# Current_DAC.net
KiCad netlist of a schematic drawn in Altium Designer
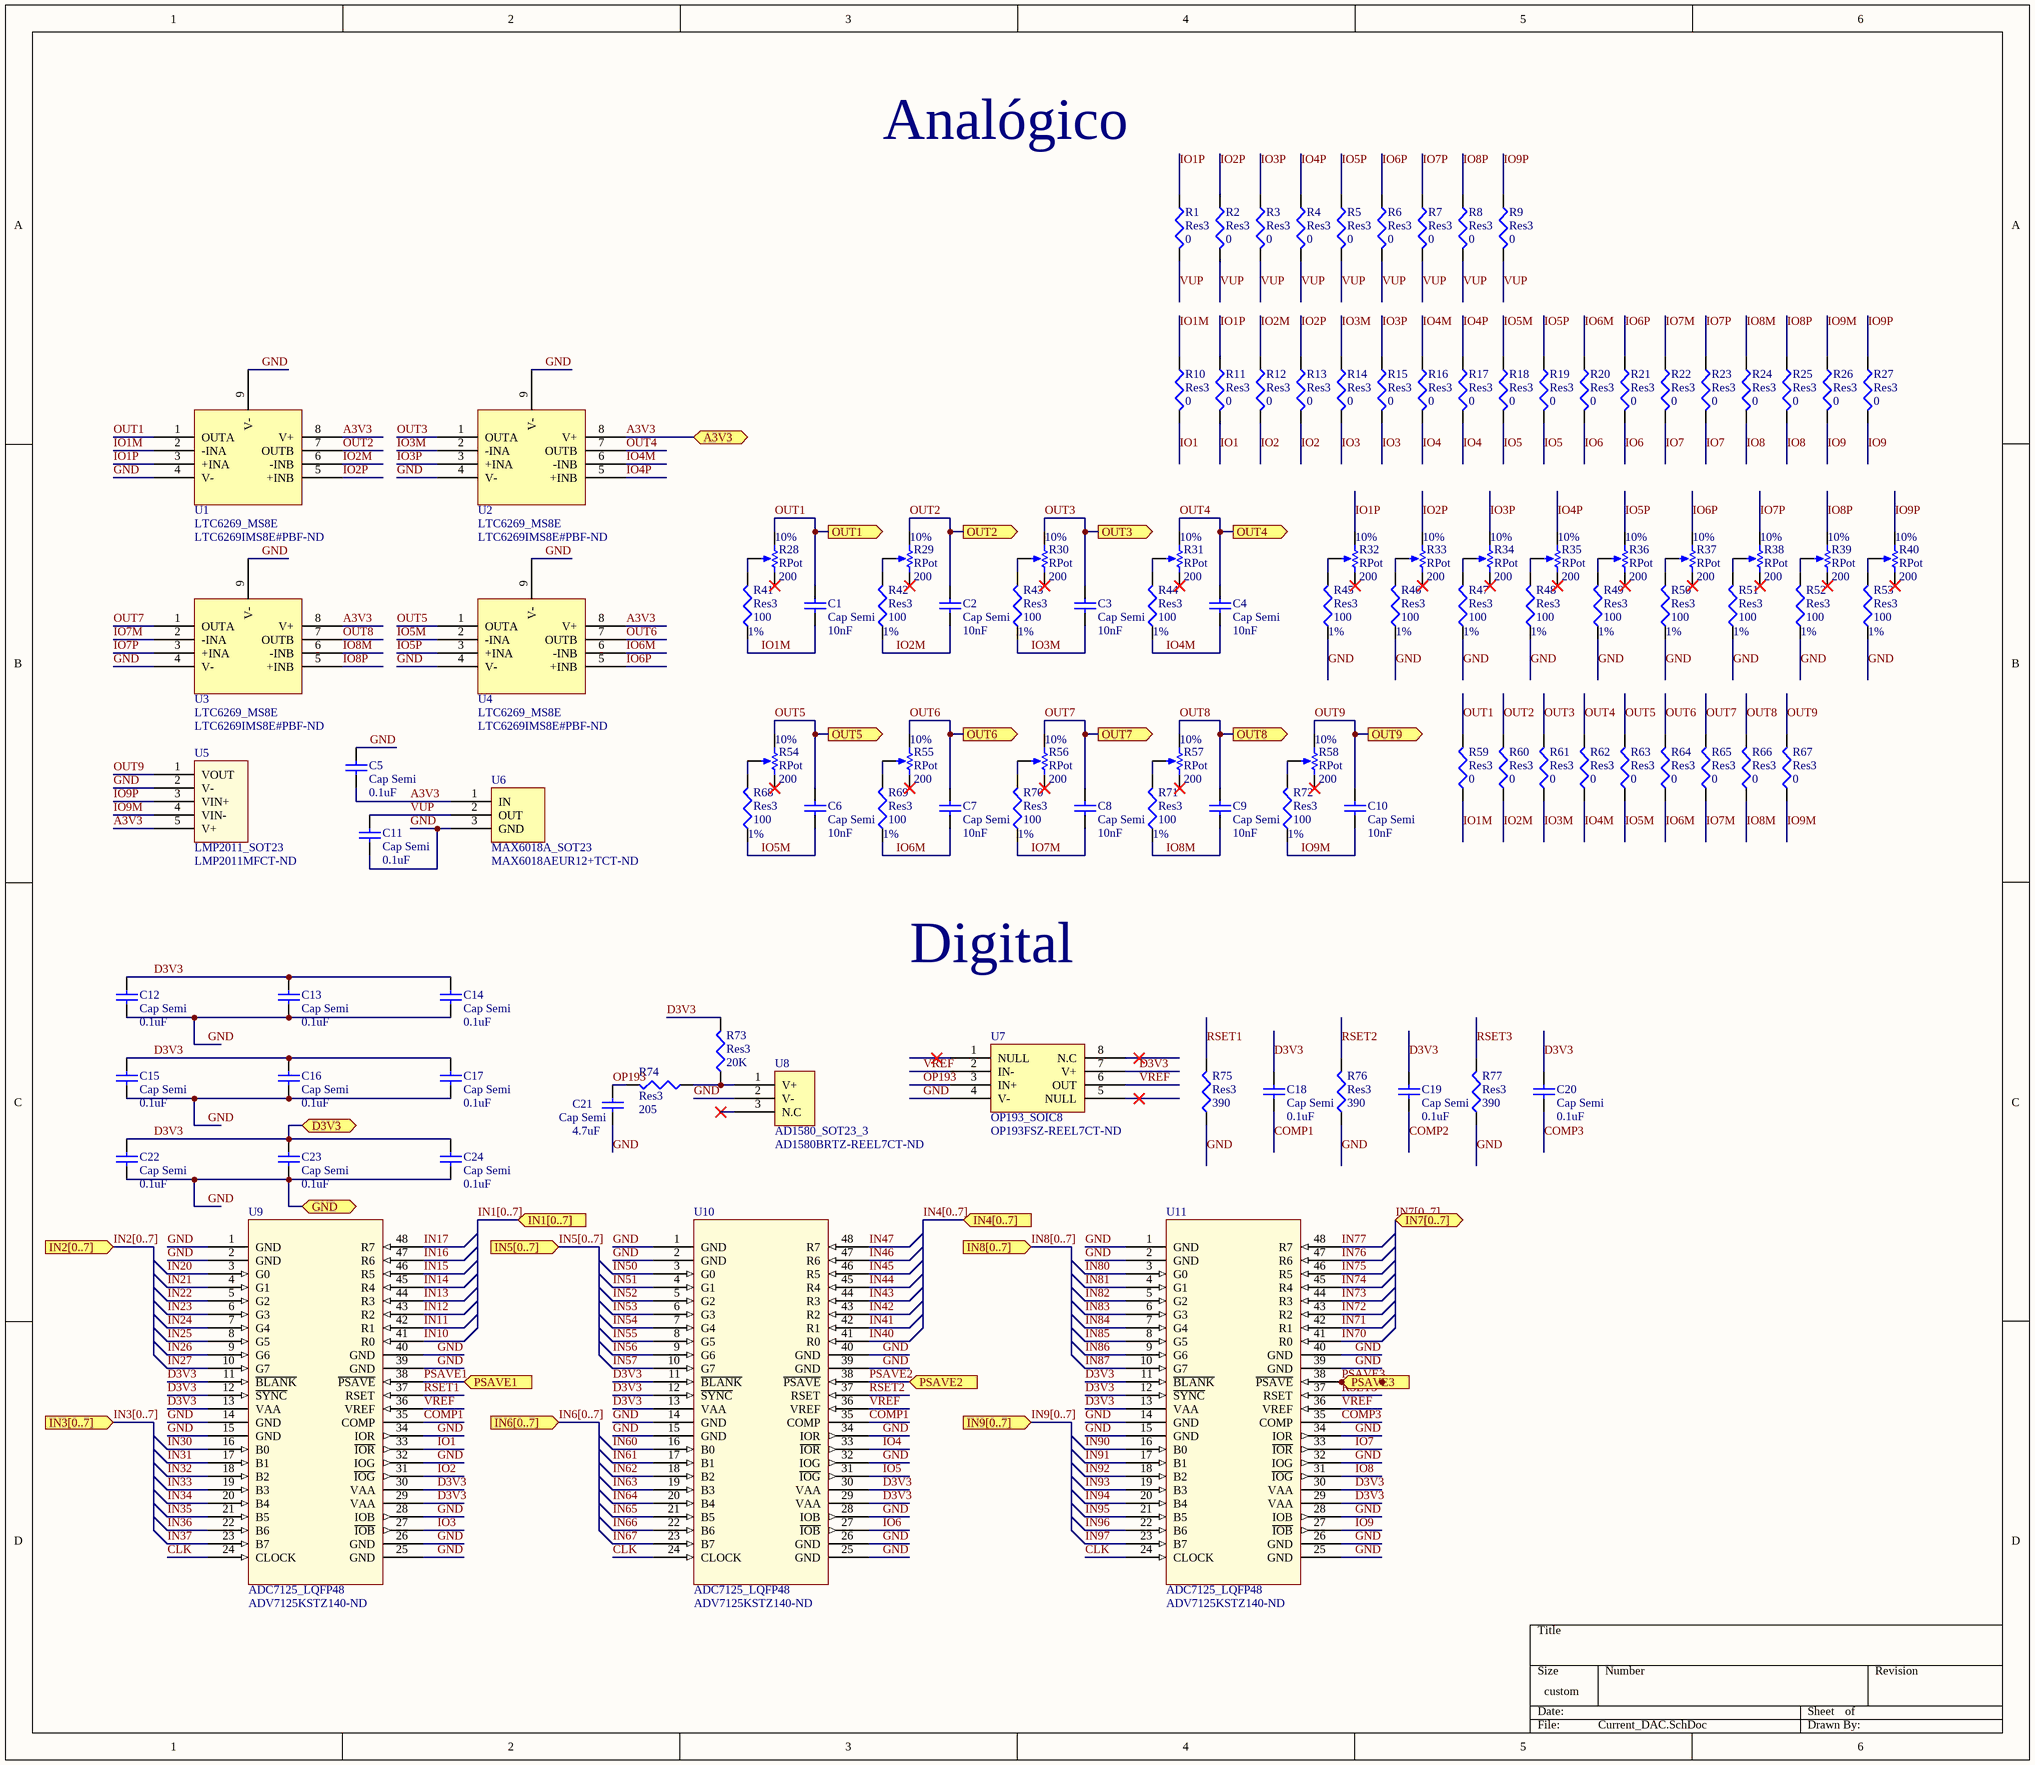
[diagram p0: Current_DAC.SchDoc]

(export (version "E")
  (design (tool "Eeschema 10.0.6"))
  (components
    (comp (ref "C1")
      (value "Cap Semi")
      (footprint "J1-0603")
      (description "Capacitor (Semiconductor SIM Model)")
      (fields (field (name "ALTIUM_VALUE") "10nF") (field (name "PUBLISHER") "Altium Limited"))
      (libsource (lib "Miscellaneous Devices") (part "Cap Semi"))
    )
    (comp (ref "C2")
      (value "Cap Semi")
      (footprint "J1-0603")
      (description "Capacitor (Semiconductor SIM Model)")
      (fields (field (name "ALTIUM_VALUE") "10nF") (field (name "PUBLISHER") "Altium Limited"))
      (libsource (lib "Miscellaneous Devices") (part "Cap Semi"))
    )
    (comp (ref "C3")
      (value "Cap Semi")
      (footprint "J1-0603")
      (description "Capacitor (Semiconductor SIM Model)")
      (fields (field (name "ALTIUM_VALUE") "10nF") (field (name "PUBLISHER") "Altium Limited"))
      (libsource (lib "Miscellaneous Devices") (part "Cap Semi"))
    )
    (comp (ref "C4")
      (value "Cap Semi")
      (footprint "J1-0603")
      (description "Capacitor (Semiconductor SIM Model)")
      (fields (field (name "ALTIUM_VALUE") "10nF") (field (name "PUBLISHER") "Altium Limited"))
      (libsource (lib "Miscellaneous Devices") (part "Cap Semi"))
    )
    (comp (ref "C5")
      (value "Cap Semi")
      (footprint "J1-0603")
      (description "Capacitor (Semiconductor SIM Model)")
      (fields (field (name "ALTIUM_VALUE") "0.1uF") (field (name "PUBLISHER") "Altium Limited"))
      (libsource (lib "Miscellaneous Devices") (part "Cap Semi"))
    )
    (comp (ref "C6")
      (value "Cap Semi")
      (footprint "J1-0603")
      (description "Capacitor (Semiconductor SIM Model)")
      (fields (field (name "ALTIUM_VALUE") "10nF") (field (name "PUBLISHER") "Altium Limited"))
      (libsource (lib "Miscellaneous Devices") (part "Cap Semi"))
    )
    (comp (ref "C7")
      (value "Cap Semi")
      (footprint "J1-0603")
      (description "Capacitor (Semiconductor SIM Model)")
      (fields (field (name "ALTIUM_VALUE") "10nF") (field (name "PUBLISHER") "Altium Limited"))
      (libsource (lib "Miscellaneous Devices") (part "Cap Semi"))
    )
    (comp (ref "C8")
      (value "Cap Semi")
      (footprint "J1-0603")
      (description "Capacitor (Semiconductor SIM Model)")
      (fields (field (name "ALTIUM_VALUE") "10nF") (field (name "PUBLISHER") "Altium Limited"))
      (libsource (lib "Miscellaneous Devices") (part "Cap Semi"))
    )
    (comp (ref "C9")
      (value "Cap Semi")
      (footprint "J1-0603")
      (description "Capacitor (Semiconductor SIM Model)")
      (fields (field (name "ALTIUM_VALUE") "10nF") (field (name "PUBLISHER") "Altium Limited"))
      (libsource (lib "Miscellaneous Devices") (part "Cap Semi"))
    )
    (comp (ref "C10")
      (value "Cap Semi")
      (footprint "J1-0603")
      (description "Capacitor (Semiconductor SIM Model)")
      (fields (field (name "ALTIUM_VALUE") "10nF") (field (name "PUBLISHER") "Altium Limited"))
      (libsource (lib "Miscellaneous Devices") (part "Cap Semi"))
    )
    (comp (ref "C11")
      (value "Cap Semi")
      (footprint "J1-0603")
      (description "Capacitor (Semiconductor SIM Model)")
      (fields (field (name "ALTIUM_VALUE") "0.1uF") (field (name "PUBLISHER") "Altium Limited"))
      (libsource (lib "Miscellaneous Devices") (part "Cap Semi"))
    )
    (comp (ref "C12")
      (value "Cap Semi")
      (footprint "J1-0603")
      (description "Capacitor (Semiconductor SIM Model)")
      (fields (field (name "ALTIUM_VALUE") "0.1uF") (field (name "PUBLISHER") "Altium Limited"))
      (libsource (lib "Miscellaneous Devices") (part "Cap Semi"))
    )
    (comp (ref "C13")
      (value "Cap Semi")
      (footprint "J1-0603")
      (description "Capacitor (Semiconductor SIM Model)")
      (fields (field (name "ALTIUM_VALUE") "0.1uF") (field (name "PUBLISHER") "Altium Limited"))
      (libsource (lib "Miscellaneous Devices") (part "Cap Semi"))
    )
    (comp (ref "C14")
      (value "Cap Semi")
      (footprint "J1-0603")
      (description "Capacitor (Semiconductor SIM Model)")
      (fields (field (name "ALTIUM_VALUE") "0.1uF") (field (name "PUBLISHER") "Altium Limited"))
      (libsource (lib "Miscellaneous Devices") (part "Cap Semi"))
    )
    (comp (ref "C15")
      (value "Cap Semi")
      (footprint "J1-0603")
      (description "Capacitor (Semiconductor SIM Model)")
      (fields (field (name "ALTIUM_VALUE") "0.1uF") (field (name "PUBLISHER") "Altium Limited"))
      (libsource (lib "Miscellaneous Devices") (part "Cap Semi"))
    )
    (comp (ref "C16")
      (value "Cap Semi")
      (footprint "J1-0603")
      (description "Capacitor (Semiconductor SIM Model)")
      (fields (field (name "ALTIUM_VALUE") "0.1uF") (field (name "PUBLISHER") "Altium Limited"))
      (libsource (lib "Miscellaneous Devices") (part "Cap Semi"))
    )
    (comp (ref "C17")
      (value "Cap Semi")
      (footprint "J1-0603")
      (description "Capacitor (Semiconductor SIM Model)")
      (fields (field (name "ALTIUM_VALUE") "0.1uF") (field (name "PUBLISHER") "Altium Limited"))
      (libsource (lib "Miscellaneous Devices") (part "Cap Semi"))
    )
    (comp (ref "C18")
      (value "Cap Semi")
      (footprint "J1-0603")
      (description "Capacitor (Semiconductor SIM Model)")
      (fields (field (name "ALTIUM_VALUE") "0.1uF") (field (name "PUBLISHER") "Altium Limited"))
      (libsource (lib "Miscellaneous Devices") (part "Cap Semi"))
    )
    (comp (ref "C19")
      (value "Cap Semi")
      (footprint "J1-0603")
      (description "Capacitor (Semiconductor SIM Model)")
      (fields (field (name "ALTIUM_VALUE") "0.1uF") (field (name "PUBLISHER") "Altium Limited"))
      (libsource (lib "Miscellaneous Devices") (part "Cap Semi"))
    )
    (comp (ref "C20")
      (value "Cap Semi")
      (footprint "J1-0603")
      (description "Capacitor (Semiconductor SIM Model)")
      (fields (field (name "ALTIUM_VALUE") "0.1uF") (field (name "PUBLISHER") "Altium Limited"))
      (libsource (lib "Miscellaneous Devices") (part "Cap Semi"))
    )
    (comp (ref "C21")
      (value "Cap Semi")
      (footprint "J1-0603")
      (description "Capacitor (Semiconductor SIM Model)")
      (fields (field (name "ALTIUM_VALUE") "4.7uF") (field (name "PUBLISHER") "Altium Limited"))
      (libsource (lib "Miscellaneous Devices") (part "Cap Semi"))
    )
    (comp (ref "C22")
      (value "Cap Semi")
      (footprint "J1-0603")
      (description "Capacitor (Semiconductor SIM Model)")
      (fields (field (name "ALTIUM_VALUE") "0.1uF") (field (name "PUBLISHER") "Altium Limited"))
      (libsource (lib "Miscellaneous Devices") (part "Cap Semi"))
    )
    (comp (ref "C23")
      (value "Cap Semi")
      (footprint "J1-0603")
      (description "Capacitor (Semiconductor SIM Model)")
      (fields (field (name "ALTIUM_VALUE") "0.1uF") (field (name "PUBLISHER") "Altium Limited"))
      (libsource (lib "Miscellaneous Devices") (part "Cap Semi"))
    )
    (comp (ref "C24")
      (value "Cap Semi")
      (footprint "J1-0603")
      (description "Capacitor (Semiconductor SIM Model)")
      (fields (field (name "ALTIUM_VALUE") "0.1uF") (field (name "PUBLISHER") "Altium Limited"))
      (libsource (lib "Miscellaneous Devices") (part "Cap Semi"))
    )
    (comp (ref "R1")
      (value "Res3")
      (footprint "J1-0603")
      (description "Resistor")
      (fields (field (name "ALTIUM_VALUE") "0") (field (name "PUBLISHER") "Altium Limited"))
      (libsource (lib "Miscellaneous Devices") (part "Res3"))
    )
    (comp (ref "R2")
      (value "Res3")
      (footprint "J1-0603")
      (description "Resistor")
      (fields (field (name "ALTIUM_VALUE") "0") (field (name "PUBLISHER") "Altium Limited"))
      (libsource (lib "Miscellaneous Devices") (part "Res3"))
    )
    (comp (ref "R3")
      (value "Res3")
      (footprint "J1-0603")
      (description "Resistor")
      (fields (field (name "ALTIUM_VALUE") "0") (field (name "PUBLISHER") "Altium Limited"))
      (libsource (lib "Miscellaneous Devices") (part "Res3"))
    )
    (comp (ref "R4")
      (value "Res3")
      (footprint "J1-0603")
      (description "Resistor")
      (fields (field (name "ALTIUM_VALUE") "0") (field (name "PUBLISHER") "Altium Limited"))
      (libsource (lib "Miscellaneous Devices") (part "Res3"))
    )
    (comp (ref "R5")
      (value "Res3")
      (footprint "J1-0603")
      (description "Resistor")
      (fields (field (name "ALTIUM_VALUE") "0") (field (name "PUBLISHER") "Altium Limited"))
      (libsource (lib "Miscellaneous Devices") (part "Res3"))
    )
    (comp (ref "R6")
      (value "Res3")
      (footprint "J1-0603")
      (description "Resistor")
      (fields (field (name "ALTIUM_VALUE") "0") (field (name "PUBLISHER") "Altium Limited"))
      (libsource (lib "Miscellaneous Devices") (part "Res3"))
    )
    (comp (ref "R7")
      (value "Res3")
      (footprint "J1-0603")
      (description "Resistor")
      (fields (field (name "ALTIUM_VALUE") "0") (field (name "PUBLISHER") "Altium Limited"))
      (libsource (lib "Miscellaneous Devices") (part "Res3"))
    )
    (comp (ref "R8")
      (value "Res3")
      (footprint "J1-0603")
      (description "Resistor")
      (fields (field (name "ALTIUM_VALUE") "0") (field (name "PUBLISHER") "Altium Limited"))
      (libsource (lib "Miscellaneous Devices") (part "Res3"))
    )
    (comp (ref "R9")
      (value "Res3")
      (footprint "J1-0603")
      (description "Resistor")
      (fields (field (name "ALTIUM_VALUE") "0") (field (name "PUBLISHER") "Altium Limited"))
      (libsource (lib "Miscellaneous Devices") (part "Res3"))
    )
    (comp (ref "R10")
      (value "Res3")
      (footprint "J1-0603")
      (description "Resistor")
      (fields (field (name "ALTIUM_VALUE") "0") (field (name "PUBLISHER") "Altium Limited"))
      (libsource (lib "Miscellaneous Devices") (part "Res3"))
    )
    (comp (ref "R11")
      (value "Res3")
      (footprint "J1-0603")
      (description "Resistor")
      (fields (field (name "ALTIUM_VALUE") "0") (field (name "PUBLISHER") "Altium Limited"))
      (libsource (lib "Miscellaneous Devices") (part "Res3"))
    )
    (comp (ref "R12")
      (value "Res3")
      (footprint "J1-0603")
      (description "Resistor")
      (fields (field (name "ALTIUM_VALUE") "0") (field (name "PUBLISHER") "Altium Limited"))
      (libsource (lib "Miscellaneous Devices") (part "Res3"))
    )
    (comp (ref "R13")
      (value "Res3")
      (footprint "J1-0603")
      (description "Resistor")
      (fields (field (name "ALTIUM_VALUE") "0") (field (name "PUBLISHER") "Altium Limited"))
      (libsource (lib "Miscellaneous Devices") (part "Res3"))
    )
    (comp (ref "R14")
      (value "Res3")
      (footprint "J1-0603")
      (description "Resistor")
      (fields (field (name "ALTIUM_VALUE") "0") (field (name "PUBLISHER") "Altium Limited"))
      (libsource (lib "Miscellaneous Devices") (part "Res3"))
    )
    (comp (ref "R15")
      (value "Res3")
      (footprint "J1-0603")
      (description "Resistor")
      (fields (field (name "ALTIUM_VALUE") "0") (field (name "PUBLISHER") "Altium Limited"))
      (libsource (lib "Miscellaneous Devices") (part "Res3"))
    )
    (comp (ref "R16")
      (value "Res3")
      (footprint "J1-0603")
      (description "Resistor")
      (fields (field (name "ALTIUM_VALUE") "0") (field (name "PUBLISHER") "Altium Limited"))
      (libsource (lib "Miscellaneous Devices") (part "Res3"))
    )
    (comp (ref "R17")
      (value "Res3")
      (footprint "J1-0603")
      (description "Resistor")
      (fields (field (name "ALTIUM_VALUE") "0") (field (name "PUBLISHER") "Altium Limited"))
      (libsource (lib "Miscellaneous Devices") (part "Res3"))
    )
    (comp (ref "R18")
      (value "Res3")
      (footprint "J1-0603")
      (description "Resistor")
      (fields (field (name "ALTIUM_VALUE") "0") (field (name "PUBLISHER") "Altium Limited"))
      (libsource (lib "Miscellaneous Devices") (part "Res3"))
    )
    (comp (ref "R19")
      (value "Res3")
      (footprint "J1-0603")
      (description "Resistor")
      (fields (field (name "ALTIUM_VALUE") "0") (field (name "PUBLISHER") "Altium Limited"))
      (libsource (lib "Miscellaneous Devices") (part "Res3"))
    )
    (comp (ref "R20")
      (value "Res3")
      (footprint "J1-0603")
      (description "Resistor")
      (fields (field (name "ALTIUM_VALUE") "0") (field (name "PUBLISHER") "Altium Limited"))
      (libsource (lib "Miscellaneous Devices") (part "Res3"))
    )
    (comp (ref "R21")
      (value "Res3")
      (footprint "J1-0603")
      (description "Resistor")
      (fields (field (name "ALTIUM_VALUE") "0") (field (name "PUBLISHER") "Altium Limited"))
      (libsource (lib "Miscellaneous Devices") (part "Res3"))
    )
    (comp (ref "R22")
      (value "Res3")
      (footprint "J1-0603")
      (description "Resistor")
      (fields (field (name "ALTIUM_VALUE") "0") (field (name "PUBLISHER") "Altium Limited"))
      (libsource (lib "Miscellaneous Devices") (part "Res3"))
    )
    (comp (ref "R23")
      (value "Res3")
      (footprint "J1-0603")
      (description "Resistor")
      (fields (field (name "ALTIUM_VALUE") "0") (field (name "PUBLISHER") "Altium Limited"))
      (libsource (lib "Miscellaneous Devices") (part "Res3"))
    )
    (comp (ref "R24")
      (value "Res3")
      (footprint "J1-0603")
      (description "Resistor")
      (fields (field (name "ALTIUM_VALUE") "0") (field (name "PUBLISHER") "Altium Limited"))
      (libsource (lib "Miscellaneous Devices") (part "Res3"))
    )
    (comp (ref "R25")
      (value "Res3")
      (footprint "J1-0603")
      (description "Resistor")
      (fields (field (name "ALTIUM_VALUE") "0") (field (name "PUBLISHER") "Altium Limited"))
      (libsource (lib "Miscellaneous Devices") (part "Res3"))
    )
    (comp (ref "R26")
      (value "Res3")
      (footprint "J1-0603")
      (description "Resistor")
      (fields (field (name "ALTIUM_VALUE") "0") (field (name "PUBLISHER") "Altium Limited"))
      (libsource (lib "Miscellaneous Devices") (part "Res3"))
    )
    (comp (ref "R27")
      (value "Res3")
      (footprint "J1-0603")
      (description "Resistor")
      (fields (field (name "ALTIUM_VALUE") "0") (field (name "PUBLISHER") "Altium Limited"))
      (libsource (lib "Miscellaneous Devices") (part "Res3"))
    )
    (comp (ref "R28")
      (value "RPot")
      (footprint "TS63Y_POT")
      (description "Potentiometer")
      (fields
        (field (name "ALTIUM_VALUE") "200")
        (field (name "TOL") "10%")
        (field (name "PUBLISHER") "Altium Limited")
      )
      (libsource (lib "Miscellaneous Devices") (part "RPot"))
    )
    (comp (ref "R29")
      (value "RPot")
      (footprint "TS63Y_POT")
      (description "Potentiometer")
      (fields
        (field (name "ALTIUM_VALUE") "200")
        (field (name "TOL") "10%")
        (field (name "PUBLISHER") "Altium Limited")
      )
      (libsource (lib "Miscellaneous Devices") (part "RPot"))
    )
    (comp (ref "R30")
      (value "RPot")
      (footprint "TS63Y_POT")
      (description "Potentiometer")
      (fields
        (field (name "ALTIUM_VALUE") "200")
        (field (name "TOL") "10%")
        (field (name "PUBLISHER") "Altium Limited")
      )
      (libsource (lib "Miscellaneous Devices") (part "RPot"))
    )
    (comp (ref "R31")
      (value "RPot")
      (footprint "TS63Y_POT")
      (description "Potentiometer")
      (fields
        (field (name "ALTIUM_VALUE") "200")
        (field (name "TOL") "10%")
        (field (name "PUBLISHER") "Altium Limited")
      )
      (libsource (lib "Miscellaneous Devices") (part "RPot"))
    )
    (comp (ref "R32")
      (value "RPot")
      (footprint "TS63Y_POT")
      (description "Potentiometer")
      (fields
        (field (name "ALTIUM_VALUE") "200")
        (field (name "TOL") "10%")
        (field (name "PUBLISHER") "Altium Limited")
      )
      (libsource (lib "Miscellaneous Devices") (part "RPot"))
    )
    (comp (ref "R33")
      (value "RPot")
      (footprint "TS63Y_POT")
      (description "Potentiometer")
      (fields
        (field (name "ALTIUM_VALUE") "200")
        (field (name "TOL") "10%")
        (field (name "PUBLISHER") "Altium Limited")
      )
      (libsource (lib "Miscellaneous Devices") (part "RPot"))
    )
    (comp (ref "R34")
      (value "RPot")
      (footprint "TS63Y_POT")
      (description "Potentiometer")
      (fields
        (field (name "ALTIUM_VALUE") "200")
        (field (name "TOL") "10%")
        (field (name "PUBLISHER") "Altium Limited")
      )
      (libsource (lib "Miscellaneous Devices") (part "RPot"))
    )
    (comp (ref "R35")
      (value "RPot")
      (footprint "TS63Y_POT")
      (description "Potentiometer")
      (fields
        (field (name "ALTIUM_VALUE") "200")
        (field (name "TOL") "10%")
        (field (name "PUBLISHER") "Altium Limited")
      )
      (libsource (lib "Miscellaneous Devices") (part "RPot"))
    )
    (comp (ref "R36")
      (value "RPot")
      (footprint "TS63Y_POT")
      (description "Potentiometer")
      (fields
        (field (name "ALTIUM_VALUE") "200")
        (field (name "TOL") "10%")
        (field (name "PUBLISHER") "Altium Limited")
      )
      (libsource (lib "Miscellaneous Devices") (part "RPot"))
    )
    (comp (ref "R37")
      (value "RPot")
      (footprint "TS63Y_POT")
      (description "Potentiometer")
      (fields
        (field (name "ALTIUM_VALUE") "200")
        (field (name "TOL") "10%")
        (field (name "PUBLISHER") "Altium Limited")
      )
      (libsource (lib "Miscellaneous Devices") (part "RPot"))
    )
    (comp (ref "R38")
      (value "RPot")
      (footprint "TS63Y_POT")
      (description "Potentiometer")
      (fields
        (field (name "ALTIUM_VALUE") "200")
        (field (name "TOL") "10%")
        (field (name "PUBLISHER") "Altium Limited")
      )
      (libsource (lib "Miscellaneous Devices") (part "RPot"))
    )
    (comp (ref "R39")
      (value "RPot")
      (footprint "TS63Y_POT")
      (description "Potentiometer")
      (fields
        (field (name "ALTIUM_VALUE") "200")
        (field (name "TOL") "10%")
        (field (name "PUBLISHER") "Altium Limited")
      )
      (libsource (lib "Miscellaneous Devices") (part "RPot"))
    )
    (comp (ref "R40")
      (value "RPot")
      (footprint "TS63Y_POT")
      (description "Potentiometer")
      (fields
        (field (name "ALTIUM_VALUE") "200")
        (field (name "TOL") "10%")
        (field (name "PUBLISHER") "Altium Limited")
      )
      (libsource (lib "Miscellaneous Devices") (part "RPot"))
    )
    (comp (ref "R41")
      (value "Res3")
      (footprint "J1-0603")
      (description "Resistor")
      (fields
        (field (name "ALTIUM_VALUE") "100")
        (field (name "TOL") "1%")
        (field (name "PUBLISHER") "Altium Limited")
      )
      (libsource (lib "Miscellaneous Devices") (part "Res3"))
    )
    (comp (ref "R42")
      (value "Res3")
      (footprint "J1-0603")
      (description "Resistor")
      (fields
        (field (name "ALTIUM_VALUE") "100")
        (field (name "TOL") "1%")
        (field (name "PUBLISHER") "Altium Limited")
      )
      (libsource (lib "Miscellaneous Devices") (part "Res3"))
    )
    (comp (ref "R43")
      (value "Res3")
      (footprint "J1-0603")
      (description "Resistor")
      (fields
        (field (name "ALTIUM_VALUE") "100")
        (field (name "TOL") "1%")
        (field (name "PUBLISHER") "Altium Limited")
      )
      (libsource (lib "Miscellaneous Devices") (part "Res3"))
    )
    (comp (ref "R44")
      (value "Res3")
      (footprint "J1-0603")
      (description "Resistor")
      (fields
        (field (name "ALTIUM_VALUE") "100")
        (field (name "TOL") "1%")
        (field (name "PUBLISHER") "Altium Limited")
      )
      (libsource (lib "Miscellaneous Devices") (part "Res3"))
    )
    (comp (ref "R45")
      (value "Res3")
      (footprint "J1-0603")
      (description "Resistor")
      (fields
        (field (name "ALTIUM_VALUE") "100")
        (field (name "TOL") "1%")
        (field (name "PUBLISHER") "Altium Limited")
      )
      (libsource (lib "Miscellaneous Devices") (part "Res3"))
    )
    (comp (ref "R46")
      (value "Res3")
      (footprint "J1-0603")
      (description "Resistor")
      (fields
        (field (name "ALTIUM_VALUE") "100")
        (field (name "TOL") "1%")
        (field (name "PUBLISHER") "Altium Limited")
      )
      (libsource (lib "Miscellaneous Devices") (part "Res3"))
    )
    (comp (ref "R47")
      (value "Res3")
      (footprint "J1-0603")
      (description "Resistor")
      (fields
        (field (name "ALTIUM_VALUE") "100")
        (field (name "TOL") "1%")
        (field (name "PUBLISHER") "Altium Limited")
      )
      (libsource (lib "Miscellaneous Devices") (part "Res3"))
    )
    (comp (ref "R48")
      (value "Res3")
      (footprint "J1-0603")
      (description "Resistor")
      (fields
        (field (name "ALTIUM_VALUE") "100")
        (field (name "TOL") "1%")
        (field (name "PUBLISHER") "Altium Limited")
      )
      (libsource (lib "Miscellaneous Devices") (part "Res3"))
    )
    (comp (ref "R49")
      (value "Res3")
      (footprint "J1-0603")
      (description "Resistor")
      (fields
        (field (name "ALTIUM_VALUE") "100")
        (field (name "TOL") "1%")
        (field (name "PUBLISHER") "Altium Limited")
      )
      (libsource (lib "Miscellaneous Devices") (part "Res3"))
    )
    (comp (ref "R50")
      (value "Res3")
      (footprint "J1-0603")
      (description "Resistor")
      (fields
        (field (name "ALTIUM_VALUE") "100")
        (field (name "TOL") "1%")
        (field (name "PUBLISHER") "Altium Limited")
      )
      (libsource (lib "Miscellaneous Devices") (part "Res3"))
    )
    (comp (ref "R51")
      (value "Res3")
      (footprint "J1-0603")
      (description "Resistor")
      (fields
        (field (name "ALTIUM_VALUE") "100")
        (field (name "TOL") "1%")
        (field (name "PUBLISHER") "Altium Limited")
      )
      (libsource (lib "Miscellaneous Devices") (part "Res3"))
    )
    (comp (ref "R52")
      (value "Res3")
      (footprint "J1-0603")
      (description "Resistor")
      (fields
        (field (name "ALTIUM_VALUE") "100")
        (field (name "TOL") "1%")
        (field (name "PUBLISHER") "Altium Limited")
      )
      (libsource (lib "Miscellaneous Devices") (part "Res3"))
    )
    (comp (ref "R53")
      (value "Res3")
      (footprint "J1-0603")
      (description "Resistor")
      (fields
        (field (name "ALTIUM_VALUE") "100")
        (field (name "TOL") "1%")
        (field (name "PUBLISHER") "Altium Limited")
      )
      (libsource (lib "Miscellaneous Devices") (part "Res3"))
    )
    (comp (ref "R54")
      (value "RPot")
      (footprint "TS63Y_POT")
      (description "Potentiometer")
      (fields
        (field (name "ALTIUM_VALUE") "200")
        (field (name "TOL") "10%")
        (field (name "PUBLISHER") "Altium Limited")
      )
      (libsource (lib "Miscellaneous Devices") (part "RPot"))
    )
    (comp (ref "R55")
      (value "RPot")
      (footprint "TS63Y_POT")
      (description "Potentiometer")
      (fields
        (field (name "ALTIUM_VALUE") "200")
        (field (name "TOL") "10%")
        (field (name "PUBLISHER") "Altium Limited")
      )
      (libsource (lib "Miscellaneous Devices") (part "RPot"))
    )
    (comp (ref "R56")
      (value "RPot")
      (footprint "TS63Y_POT")
      (description "Potentiometer")
      (fields
        (field (name "ALTIUM_VALUE") "200")
        (field (name "TOL") "10%")
        (field (name "PUBLISHER") "Altium Limited")
      )
      (libsource (lib "Miscellaneous Devices") (part "RPot"))
    )
    (comp (ref "R57")
      (value "RPot")
      (footprint "TS63Y_POT")
      (description "Potentiometer")
      (fields
        (field (name "ALTIUM_VALUE") "200")
        (field (name "TOL") "10%")
        (field (name "PUBLISHER") "Altium Limited")
      )
      (libsource (lib "Miscellaneous Devices") (part "RPot"))
    )
    (comp (ref "R58")
      (value "RPot")
      (footprint "TS63Y_POT")
      (description "Potentiometer")
      (fields
        (field (name "ALTIUM_VALUE") "200")
        (field (name "TOL") "10%")
        (field (name "PUBLISHER") "Altium Limited")
      )
      (libsource (lib "Miscellaneous Devices") (part "RPot"))
    )
    (comp (ref "R59")
      (value "Res3")
      (footprint "J1-0603")
      (description "Resistor")
      (fields (field (name "ALTIUM_VALUE") "0") (field (name "PUBLISHER") "Altium Limited"))
      (libsource (lib "Miscellaneous Devices") (part "Res3"))
    )
    (comp (ref "R60")
      (value "Res3")
      (footprint "J1-0603")
      (description "Resistor")
      (fields (field (name "ALTIUM_VALUE") "0") (field (name "PUBLISHER") "Altium Limited"))
      (libsource (lib "Miscellaneous Devices") (part "Res3"))
    )
    (comp (ref "R61")
      (value "Res3")
      (footprint "J1-0603")
      (description "Resistor")
      (fields (field (name "ALTIUM_VALUE") "0") (field (name "PUBLISHER") "Altium Limited"))
      (libsource (lib "Miscellaneous Devices") (part "Res3"))
    )
    (comp (ref "R62")
      (value "Res3")
      (footprint "J1-0603")
      (description "Resistor")
      (fields (field (name "ALTIUM_VALUE") "0") (field (name "PUBLISHER") "Altium Limited"))
      (libsource (lib "Miscellaneous Devices") (part "Res3"))
    )
    (comp (ref "R63")
      (value "Res3")
      (footprint "J1-0603")
      (description "Resistor")
      (fields (field (name "ALTIUM_VALUE") "0") (field (name "PUBLISHER") "Altium Limited"))
      (libsource (lib "Miscellaneous Devices") (part "Res3"))
    )
    (comp (ref "R64")
      (value "Res3")
      (footprint "J1-0603")
      (description "Resistor")
      (fields (field (name "ALTIUM_VALUE") "0") (field (name "PUBLISHER") "Altium Limited"))
      (libsource (lib "Miscellaneous Devices") (part "Res3"))
    )
    (comp (ref "R65")
      (value "Res3")
      (footprint "J1-0603")
      (description "Resistor")
      (fields (field (name "ALTIUM_VALUE") "0") (field (name "PUBLISHER") "Altium Limited"))
      (libsource (lib "Miscellaneous Devices") (part "Res3"))
    )
    (comp (ref "R66")
      (value "Res3")
      (footprint "J1-0603")
      (description "Resistor")
      (fields (field (name "ALTIUM_VALUE") "0") (field (name "PUBLISHER") "Altium Limited"))
      (libsource (lib "Miscellaneous Devices") (part "Res3"))
    )
    (comp (ref "R67")
      (value "Res3")
      (footprint "J1-0603")
      (description "Resistor")
      (fields (field (name "ALTIUM_VALUE") "0") (field (name "PUBLISHER") "Altium Limited"))
      (libsource (lib "Miscellaneous Devices") (part "Res3"))
    )
    (comp (ref "R68")
      (value "Res3")
      (footprint "J1-0603")
      (description "Resistor")
      (fields
        (field (name "ALTIUM_VALUE") "100")
        (field (name "TOL") "1%")
        (field (name "PUBLISHER") "Altium Limited")
      )
      (libsource (lib "Miscellaneous Devices") (part "Res3"))
    )
    (comp (ref "R69")
      (value "Res3")
      (footprint "J1-0603")
      (description "Resistor")
      (fields
        (field (name "ALTIUM_VALUE") "100")
        (field (name "TOL") "1%")
        (field (name "PUBLISHER") "Altium Limited")
      )
      (libsource (lib "Miscellaneous Devices") (part "Res3"))
    )
    (comp (ref "R70")
      (value "Res3")
      (footprint "J1-0603")
      (description "Resistor")
      (fields
        (field (name "ALTIUM_VALUE") "100")
        (field (name "TOL") "1%")
        (field (name "PUBLISHER") "Altium Limited")
      )
      (libsource (lib "Miscellaneous Devices") (part "Res3"))
    )
    (comp (ref "R71")
      (value "Res3")
      (footprint "J1-0603")
      (description "Resistor")
      (fields
        (field (name "ALTIUM_VALUE") "100")
        (field (name "TOL") "1%")
        (field (name "PUBLISHER") "Altium Limited")
      )
      (libsource (lib "Miscellaneous Devices") (part "Res3"))
    )
    (comp (ref "R72")
      (value "Res3")
      (footprint "J1-0603")
      (description "Resistor")
      (fields
        (field (name "ALTIUM_VALUE") "100")
        (field (name "TOL") "1%")
        (field (name "PUBLISHER") "Altium Limited")
      )
      (libsource (lib "Miscellaneous Devices") (part "Res3"))
    )
    (comp (ref "R73")
      (value "Res3")
      (footprint "J1-0603")
      (description "Resistor")
      (fields (field (name "ALTIUM_VALUE") "20K") (field (name "PUBLISHER") "Altium Limited"))
      (libsource (lib "Miscellaneous Devices") (part "Res3"))
    )
    (comp (ref "R74")
      (value "Res3")
      (footprint "J1-0603")
      (description "Resistor")
      (fields (field (name "ALTIUM_VALUE") "205") (field (name "PUBLISHER") "Altium Limited"))
      (libsource (lib "Miscellaneous Devices") (part "Res3"))
    )
    (comp (ref "R75")
      (value "Res3")
      (footprint "J1-0603")
      (description "Resistor")
      (fields (field (name "ALTIUM_VALUE") "390") (field (name "PUBLISHER") "Altium Limited"))
      (libsource (lib "Miscellaneous Devices") (part "Res3"))
    )
    (comp (ref "R76")
      (value "Res3")
      (footprint "J1-0603")
      (description "Resistor")
      (fields (field (name "ALTIUM_VALUE") "390") (field (name "PUBLISHER") "Altium Limited"))
      (libsource (lib "Miscellaneous Devices") (part "Res3"))
    )
    (comp (ref "R77")
      (value "Res3")
      (footprint "J1-0603")
      (description "Resistor")
      (fields (field (name "ALTIUM_VALUE") "390") (field (name "PUBLISHER") "Altium Limited"))
      (libsource (lib "Miscellaneous Devices") (part "Res3"))
    )
    (comp (ref "U1")
      (value "LTC6269_MS8E")
      (footprint "LTC6269_MSOP8")
      (fields (field (name "SUPPLIER PART NUMBER 1") "LTC6269IMS8E#PBF-ND"))
      (libsource (lib "Lib1") (part "LTC6269_MS8E"))
    )
    (comp (ref "U2")
      (value "LTC6269_MS8E")
      (footprint "LTC6269_MSOP8")
      (fields (field (name "SUPPLIER PART NUMBER 1") "LTC6269IMS8E#PBF-ND"))
      (libsource (lib "Lib1") (part "LTC6269_MS8E"))
    )
    (comp (ref "U3")
      (value "LTC6269_MS8E")
      (footprint "LTC6269_MSOP8")
      (fields (field (name "SUPPLIER PART NUMBER 1") "LTC6269IMS8E#PBF-ND"))
      (libsource (lib "Lib1") (part "LTC6269_MS8E"))
    )
    (comp (ref "U4")
      (value "LTC6269_MS8E")
      (footprint "LTC6269_MSOP8")
      (fields (field (name "SUPPLIER PART NUMBER 1") "LTC6269IMS8E#PBF-ND"))
      (libsource (lib "Lib1") (part "LTC6269_MS8E"))
    )
    (comp (ref "U5")
      (value "LMP2011_SOT23")
      (footprint "LMP2011_SOT23")
      (fields (field (name "SUPPLIER PART NUMBER 1") "LMP2011MFCT-ND"))
      (libsource (lib "Lib1") (part "LMP2011_SOT23"))
    )
    (comp (ref "U6")
      (value "MAX6018A_SOT23")
      (footprint "MAX6018A_SOT23")
      (fields (field (name "SUPPLIER PART NUMBER 1") "MAX6018AEUR12+TCT-ND"))
      (libsource (lib "Lib1") (part "MAX6018A_SOT23"))
    )
    (comp (ref "U7")
      (value "OP193_SOIC8")
      (footprint "OP193_SOIC8")
      (fields (field (name "SUPPLIER PART NUMBER 1") "OP193FSZ-REEL7CT-ND"))
      (libsource (lib "Lib1") (part "OP193_SOIC8"))
    )
    (comp (ref "U8")
      (value "AD1580_SOT23_3")
      (footprint "AD1580_SOT23_3")
      (fields (field (name "SUPPLIER PART NUMBER 1") "AD1580BRTZ-REEL7CT-ND"))
      (libsource (lib "Lib1") (part "AD1580_SOT23_3"))
    )
    (comp (ref "U9")
      (value "ADC7125_LQFP48")
      (footprint "ADV7125_LQFP48")
      (fields (field (name "SUPPLIER PART NUMBER 1") "ADV7125KSTZ140-ND"))
      (libsource (lib "Lib1") (part "ADC7125_LQFP48"))
    )
    (comp (ref "U10")
      (value "ADC7125_LQFP48")
      (footprint "ADV7125_LQFP48")
      (fields (field (name "SUPPLIER PART NUMBER 1") "ADV7125KSTZ140-ND"))
      (libsource (lib "Lib1") (part "ADC7125_LQFP48"))
    )
    (comp (ref "U11")
      (value "ADC7125_LQFP48")
      (footprint "ADV7125_LQFP48")
      (fields (field (name "SUPPLIER PART NUMBER 1") "ADV7125KSTZ140-ND"))
      (libsource (lib "Lib1") (part "ADC7125_LQFP48"))
    )
  )
  (nets
    (net (code "1") (name "/A3V3") (class "Default")
      (node (ref "C5") (pin "1") (pinfunction "1_1") (pintype "passive"))
      (node (ref "U1") (pin "8") (pinfunction "V+_8") (pintype "passive"))
      (node (ref "U2") (pin "8") (pinfunction "V+_8") (pintype "passive"))
      (node (ref "U3") (pin "8") (pinfunction "V+_8") (pintype "passive"))
      (node (ref "U4") (pin "8") (pinfunction "V+_8") (pintype "passive"))
      (node (ref "U5") (pin "5") (pinfunction "V+_5") (pintype "passive"))
      (node (ref "U6") (pin "1") (pinfunction "IN_1") (pintype "passive"))
    )
    (net (code "2") (name "/CLK") (class "Default")
      (node (ref "U10") (pin "24") (pinfunction "CLOCK_24") (pintype "input"))
      (node (ref "U11") (pin "24") (pinfunction "CLOCK_24") (pintype "input"))
      (node (ref "U9") (pin "24") (pinfunction "CLOCK_24") (pintype "input"))
    )
    (net (code "3") (name "/COMP1") (class "Default")
      (node (ref "C18") (pin "1") (pinfunction "1_1") (pintype "passive"))
      (node (ref "U10") (pin "35") (pinfunction "COMP_35") (pintype "passive"))
      (node (ref "U9") (pin "35") (pinfunction "COMP_35") (pintype "passive"))
    )
    (net (code "4") (name "/COMP2") (class "Default")
      (node (ref "C19") (pin "1") (pinfunction "1_1") (pintype "passive"))
    )
    (net (code "5") (name "/COMP3") (class "Default")
      (node (ref "C20") (pin "1") (pinfunction "1_1") (pintype "passive"))
      (node (ref "U11") (pin "35") (pinfunction "COMP_35") (pintype "passive"))
    )
    (net (code "6") (name "/D3V3") (class "Default")
      (node (ref "C12") (pin "1") (pinfunction "1_1") (pintype "passive"))
      (node (ref "C13") (pin "1") (pinfunction "1_1") (pintype "passive"))
      (node (ref "C14") (pin "1") (pinfunction "1_1") (pintype "passive"))
      (node (ref "C15") (pin "1") (pinfunction "1_1") (pintype "passive"))
      (node (ref "C16") (pin "1") (pinfunction "1_1") (pintype "passive"))
      (node (ref "C17") (pin "1") (pinfunction "1_1") (pintype "passive"))
      (node (ref "C18") (pin "2") (pinfunction "2_2") (pintype "passive"))
      (node (ref "C19") (pin "2") (pinfunction "2_2") (pintype "passive"))
      (node (ref "C20") (pin "2") (pinfunction "2_2") (pintype "passive"))
      (node (ref "C22") (pin "1") (pinfunction "1_1") (pintype "passive"))
      (node (ref "C23") (pin "1") (pinfunction "1_1") (pintype "passive"))
      (node (ref "C24") (pin "1") (pinfunction "1_1") (pintype "passive"))
      (node (ref "R73") (pin "2") (pinfunction "2_2") (pintype "passive"))
      (node (ref "U10") (pin "11") (pinfunction "~{BLANK}_11") (pintype "input"))
      (node (ref "U10") (pin "12") (pinfunction "~{SYNC}_12") (pintype "input"))
      (node (ref "U10") (pin "13") (pinfunction "VAA_13") (pintype "power_in"))
      (node (ref "U10") (pin "29") (pinfunction "VAA_29") (pintype "power_in"))
      (node (ref "U10") (pin "30") (pinfunction "VAA_30") (pintype "power_in"))
      (node (ref "U11") (pin "11") (pinfunction "~{BLANK}_11") (pintype "input"))
      (node (ref "U11") (pin "12") (pinfunction "~{SYNC}_12") (pintype "input"))
      (node (ref "U11") (pin "13") (pinfunction "VAA_13") (pintype "power_in"))
      (node (ref "U11") (pin "29") (pinfunction "VAA_29") (pintype "power_in"))
      (node (ref "U11") (pin "30") (pinfunction "VAA_30") (pintype "power_in"))
      (node (ref "U7") (pin "7") (pinfunction "V+_7") (pintype "passive"))
      (node (ref "U9") (pin "11") (pinfunction "~{BLANK}_11") (pintype "input"))
      (node (ref "U9") (pin "12") (pinfunction "~{SYNC}_12") (pintype "input"))
      (node (ref "U9") (pin "13") (pinfunction "VAA_13") (pintype "power_in"))
      (node (ref "U9") (pin "29") (pinfunction "VAA_29") (pintype "power_in"))
      (node (ref "U9") (pin "30") (pinfunction "VAA_30") (pintype "power_in"))
    )
    (net (code "7") (name "/GND") (class "Default")
      (node (ref "C11") (pin "1") (pinfunction "1_1") (pintype "passive"))
      (node (ref "C12") (pin "2") (pinfunction "2_2") (pintype "passive"))
      (node (ref "C13") (pin "2") (pinfunction "2_2") (pintype "passive"))
      (node (ref "C14") (pin "2") (pinfunction "2_2") (pintype "passive"))
      (node (ref "C15") (pin "2") (pinfunction "2_2") (pintype "passive"))
      (node (ref "C16") (pin "2") (pinfunction "2_2") (pintype "passive"))
      (node (ref "C17") (pin "2") (pinfunction "2_2") (pintype "passive"))
      (node (ref "C21") (pin "1") (pinfunction "1_1") (pintype "passive"))
      (node (ref "C22") (pin "2") (pinfunction "2_2") (pintype "passive"))
      (node (ref "C23") (pin "2") (pinfunction "2_2") (pintype "passive"))
      (node (ref "C24") (pin "2") (pinfunction "2_2") (pintype "passive"))
      (node (ref "C5") (pin "2") (pinfunction "2_2") (pintype "passive"))
      (node (ref "R45") (pin "1") (pinfunction "1_1") (pintype "passive"))
      (node (ref "R46") (pin "1") (pinfunction "1_1") (pintype "passive"))
      (node (ref "R47") (pin "1") (pinfunction "1_1") (pintype "passive"))
      (node (ref "R48") (pin "1") (pinfunction "1_1") (pintype "passive"))
      (node (ref "R49") (pin "1") (pinfunction "1_1") (pintype "passive"))
      (node (ref "R50") (pin "1") (pinfunction "1_1") (pintype "passive"))
      (node (ref "R51") (pin "1") (pinfunction "1_1") (pintype "passive"))
      (node (ref "R52") (pin "1") (pinfunction "1_1") (pintype "passive"))
      (node (ref "R53") (pin "1") (pinfunction "1_1") (pintype "passive"))
      (node (ref "R75") (pin "1") (pinfunction "1_1") (pintype "passive"))
      (node (ref "R76") (pin "1") (pinfunction "1_1") (pintype "passive"))
      (node (ref "R77") (pin "1") (pinfunction "1_1") (pintype "passive"))
      (node (ref "U1") (pin "4") (pinfunction "V-_4") (pintype "passive"))
      (node (ref "U1") (pin "9") (pinfunction "V-_9") (pintype "passive"))
      (node (ref "U10") (pin "1") (pinfunction "GND_1") (pintype "power_in"))
      (node (ref "U10") (pin "14") (pinfunction "GND_14") (pintype "power_in"))
      (node (ref "U10") (pin "15") (pinfunction "GND_15") (pintype "power_in"))
      (node (ref "U10") (pin "2") (pinfunction "GND_2") (pintype "power_in"))
      (node (ref "U10") (pin "25") (pinfunction "GND_25") (pintype "power_in"))
      (node (ref "U10") (pin "26") (pinfunction "GND_26") (pintype "power_in"))
      (node (ref "U10") (pin "28") (pinfunction "IOB_28") (pintype "output"))
      (node (ref "U10") (pin "32") (pinfunction "IOG_32") (pintype "output"))
      (node (ref "U10") (pin "34") (pinfunction "IOR_34") (pintype "output"))
      (node (ref "U10") (pin "39") (pinfunction "GND_39") (pintype "power_in"))
      (node (ref "U10") (pin "40") (pinfunction "GND_40") (pintype "power_in"))
      (node (ref "U11") (pin "1") (pinfunction "GND_1") (pintype "power_in"))
      (node (ref "U11") (pin "14") (pinfunction "GND_14") (pintype "power_in"))
      (node (ref "U11") (pin "15") (pinfunction "GND_15") (pintype "power_in"))
      (node (ref "U11") (pin "2") (pinfunction "GND_2") (pintype "power_in"))
      (node (ref "U11") (pin "25") (pinfunction "GND_25") (pintype "power_in"))
      (node (ref "U11") (pin "26") (pinfunction "GND_26") (pintype "power_in"))
      (node (ref "U11") (pin "28") (pinfunction "IOB_28") (pintype "output"))
      (node (ref "U11") (pin "32") (pinfunction "IOG_32") (pintype "output"))
      (node (ref "U11") (pin "34") (pinfunction "IOR_34") (pintype "output"))
      (node (ref "U11") (pin "39") (pinfunction "GND_39") (pintype "power_in"))
      (node (ref "U11") (pin "40") (pinfunction "GND_40") (pintype "power_in"))
      (node (ref "U2") (pin "4") (pinfunction "V-_4") (pintype "passive"))
      (node (ref "U2") (pin "9") (pinfunction "V-_9") (pintype "passive"))
      (node (ref "U3") (pin "4") (pinfunction "V-_4") (pintype "passive"))
      (node (ref "U3") (pin "9") (pinfunction "V-_9") (pintype "passive"))
      (node (ref "U4") (pin "4") (pinfunction "V-_4") (pintype "passive"))
      (node (ref "U4") (pin "9") (pinfunction "V-_9") (pintype "passive"))
      (node (ref "U5") (pin "2") (pinfunction "V-_2") (pintype "passive"))
      (node (ref "U6") (pin "3") (pinfunction "GND_3") (pintype "passive"))
      (node (ref "U7") (pin "4") (pinfunction "V-_4") (pintype "passive"))
      (node (ref "U8") (pin "2") (pinfunction "V-_2") (pintype "passive"))
      (node (ref "U9") (pin "1") (pinfunction "GND_1") (pintype "power_in"))
      (node (ref "U9") (pin "14") (pinfunction "GND_14") (pintype "power_in"))
      (node (ref "U9") (pin "15") (pinfunction "GND_15") (pintype "power_in"))
      (node (ref "U9") (pin "2") (pinfunction "GND_2") (pintype "power_in"))
      (node (ref "U9") (pin "25") (pinfunction "GND_25") (pintype "power_in"))
      (node (ref "U9") (pin "26") (pinfunction "GND_26") (pintype "power_in"))
      (node (ref "U9") (pin "28") (pinfunction "IOB_28") (pintype "output"))
      (node (ref "U9") (pin "32") (pinfunction "IOG_32") (pintype "output"))
      (node (ref "U9") (pin "34") (pinfunction "IOR_34") (pintype "output"))
      (node (ref "U9") (pin "39") (pinfunction "GND_39") (pintype "power_in"))
      (node (ref "U9") (pin "40") (pinfunction "GND_40") (pintype "power_in"))
    )
    (net (code "17") (name "/IN10") (class "Default")
      (node (ref "U9") (pin "41") (pinfunction "R0_41") (pintype "input"))
    )
    (net (code "18") (name "/IN11") (class "Default")
      (node (ref "U9") (pin "42") (pinfunction "R1_42") (pintype "input"))
    )
    (net (code "19") (name "/IN12") (class "Default")
      (node (ref "U9") (pin "43") (pinfunction "R2_43") (pintype "input"))
    )
    (net (code "20") (name "/IN13") (class "Default")
      (node (ref "U9") (pin "44") (pinfunction "R3_44") (pintype "input"))
    )
    (net (code "21") (name "/IN14") (class "Default")
      (node (ref "U9") (pin "45") (pinfunction "R4_45") (pintype "input"))
    )
    (net (code "22") (name "/IN15") (class "Default")
      (node (ref "U9") (pin "46") (pinfunction "R5_46") (pintype "input"))
    )
    (net (code "23") (name "/IN16") (class "Default")
      (node (ref "U9") (pin "47") (pinfunction "R6_47") (pintype "input"))
    )
    (net (code "24") (name "/IN17") (class "Default")
      (node (ref "U9") (pin "48") (pinfunction "R7_48") (pintype "input"))
    )
    (net (code "25") (name "/IN20") (class "Default")
      (node (ref "U9") (pin "3") (pinfunction "G0_3") (pintype "input"))
    )
    (net (code "26") (name "/IN21") (class "Default")
      (node (ref "U9") (pin "4") (pinfunction "G1_4") (pintype "input"))
    )
    (net (code "27") (name "/IN22") (class "Default")
      (node (ref "U9") (pin "5") (pinfunction "G2_5") (pintype "input"))
    )
    (net (code "28") (name "/IN23") (class "Default")
      (node (ref "U9") (pin "6") (pinfunction "G3_6") (pintype "input"))
    )
    (net (code "29") (name "/IN24") (class "Default")
      (node (ref "U9") (pin "7") (pinfunction "G4_7") (pintype "input"))
    )
    (net (code "30") (name "/IN25") (class "Default")
      (node (ref "U9") (pin "8") (pinfunction "G5_8") (pintype "input"))
    )
    (net (code "31") (name "/IN26") (class "Default")
      (node (ref "U9") (pin "9") (pinfunction "G6_9") (pintype "input"))
    )
    (net (code "32") (name "/IN27") (class "Default")
      (node (ref "U9") (pin "10") (pinfunction "G7_10") (pintype "input"))
    )
    (net (code "33") (name "/IN30") (class "Default")
      (node (ref "U9") (pin "16") (pinfunction "B0_16") (pintype "input"))
    )
    (net (code "34") (name "/IN31") (class "Default")
      (node (ref "U9") (pin "17") (pinfunction "B1_17") (pintype "input"))
    )
    (net (code "35") (name "/IN32") (class "Default")
      (node (ref "U9") (pin "18") (pinfunction "B2_18") (pintype "input"))
    )
    (net (code "36") (name "/IN33") (class "Default")
      (node (ref "U9") (pin "19") (pinfunction "B3_19") (pintype "input"))
    )
    (net (code "37") (name "/IN34") (class "Default")
      (node (ref "U9") (pin "20") (pinfunction "B4_20") (pintype "input"))
    )
    (net (code "38") (name "/IN35") (class "Default")
      (node (ref "U9") (pin "21") (pinfunction "B5_21") (pintype "input"))
    )
    (net (code "39") (name "/IN36") (class "Default")
      (node (ref "U9") (pin "22") (pinfunction "B6_22") (pintype "input"))
    )
    (net (code "40") (name "/IN37") (class "Default")
      (node (ref "U9") (pin "23") (pinfunction "B7_23") (pintype "input"))
    )
    (net (code "41") (name "/IN40") (class "Default")
      (node (ref "U10") (pin "41") (pinfunction "R0_41") (pintype "input"))
    )
    (net (code "42") (name "/IN41") (class "Default")
      (node (ref "U10") (pin "42") (pinfunction "R1_42") (pintype "input"))
    )
    (net (code "43") (name "/IN42") (class "Default")
      (node (ref "U10") (pin "43") (pinfunction "R2_43") (pintype "input"))
    )
    (net (code "44") (name "/IN43") (class "Default")
      (node (ref "U10") (pin "44") (pinfunction "R3_44") (pintype "input"))
    )
    (net (code "45") (name "/IN44") (class "Default")
      (node (ref "U10") (pin "45") (pinfunction "R4_45") (pintype "input"))
    )
    (net (code "46") (name "/IN45") (class "Default")
      (node (ref "U10") (pin "46") (pinfunction "R5_46") (pintype "input"))
    )
    (net (code "47") (name "/IN46") (class "Default")
      (node (ref "U10") (pin "47") (pinfunction "R6_47") (pintype "input"))
    )
    (net (code "48") (name "/IN47") (class "Default")
      (node (ref "U10") (pin "48") (pinfunction "R7_48") (pintype "input"))
    )
    (net (code "49") (name "/IN50") (class "Default")
      (node (ref "U10") (pin "3") (pinfunction "G0_3") (pintype "input"))
    )
    (net (code "50") (name "/IN51") (class "Default")
      (node (ref "U10") (pin "4") (pinfunction "G1_4") (pintype "input"))
    )
    (net (code "51") (name "/IN52") (class "Default")
      (node (ref "U10") (pin "5") (pinfunction "G2_5") (pintype "input"))
    )
    (net (code "52") (name "/IN53") (class "Default")
      (node (ref "U10") (pin "6") (pinfunction "G3_6") (pintype "input"))
    )
    (net (code "53") (name "/IN54") (class "Default")
      (node (ref "U10") (pin "7") (pinfunction "G4_7") (pintype "input"))
    )
    (net (code "54") (name "/IN55") (class "Default")
      (node (ref "U10") (pin "8") (pinfunction "G5_8") (pintype "input"))
    )
    (net (code "55") (name "/IN56") (class "Default")
      (node (ref "U10") (pin "9") (pinfunction "G6_9") (pintype "input"))
    )
    (net (code "56") (name "/IN57") (class "Default")
      (node (ref "U10") (pin "10") (pinfunction "G7_10") (pintype "input"))
    )
    (net (code "57") (name "/IN60") (class "Default")
      (node (ref "U10") (pin "16") (pinfunction "B0_16") (pintype "input"))
    )
    (net (code "58") (name "/IN61") (class "Default")
      (node (ref "U10") (pin "17") (pinfunction "B1_17") (pintype "input"))
    )
    (net (code "59") (name "/IN62") (class "Default")
      (node (ref "U10") (pin "18") (pinfunction "B2_18") (pintype "input"))
    )
    (net (code "60") (name "/IN63") (class "Default")
      (node (ref "U10") (pin "19") (pinfunction "B3_19") (pintype "input"))
    )
    (net (code "61") (name "/IN64") (class "Default")
      (node (ref "U10") (pin "20") (pinfunction "B4_20") (pintype "input"))
    )
    (net (code "62") (name "/IN65") (class "Default")
      (node (ref "U10") (pin "21") (pinfunction "B5_21") (pintype "input"))
    )
    (net (code "63") (name "/IN66") (class "Default")
      (node (ref "U10") (pin "22") (pinfunction "B6_22") (pintype "input"))
    )
    (net (code "64") (name "/IN67") (class "Default")
      (node (ref "U10") (pin "23") (pinfunction "B7_23") (pintype "input"))
    )
    (net (code "65") (name "/IN70") (class "Default")
      (node (ref "U11") (pin "41") (pinfunction "R0_41") (pintype "input"))
    )
    (net (code "66") (name "/IN71") (class "Default")
      (node (ref "U11") (pin "42") (pinfunction "R1_42") (pintype "input"))
    )
    (net (code "67") (name "/IN72") (class "Default")
      (node (ref "U11") (pin "43") (pinfunction "R2_43") (pintype "input"))
    )
    (net (code "68") (name "/IN73") (class "Default")
      (node (ref "U11") (pin "44") (pinfunction "R3_44") (pintype "input"))
    )
    (net (code "69") (name "/IN74") (class "Default")
      (node (ref "U11") (pin "45") (pinfunction "R4_45") (pintype "input"))
    )
    (net (code "70") (name "/IN75") (class "Default")
      (node (ref "U11") (pin "46") (pinfunction "R5_46") (pintype "input"))
    )
    (net (code "71") (name "/IN76") (class "Default")
      (node (ref "U11") (pin "47") (pinfunction "R6_47") (pintype "input"))
    )
    (net (code "72") (name "/IN77") (class "Default")
      (node (ref "U11") (pin "48") (pinfunction "R7_48") (pintype "input"))
    )
    (net (code "73") (name "/IN80") (class "Default")
      (node (ref "U11") (pin "3") (pinfunction "G0_3") (pintype "input"))
    )
    (net (code "74") (name "/IN81") (class "Default")
      (node (ref "U11") (pin "4") (pinfunction "G1_4") (pintype "input"))
    )
    (net (code "75") (name "/IN82") (class "Default")
      (node (ref "U11") (pin "5") (pinfunction "G2_5") (pintype "input"))
    )
    (net (code "76") (name "/IN83") (class "Default")
      (node (ref "U11") (pin "6") (pinfunction "G3_6") (pintype "input"))
    )
    (net (code "77") (name "/IN84") (class "Default")
      (node (ref "U11") (pin "7") (pinfunction "G4_7") (pintype "input"))
    )
    (net (code "78") (name "/IN85") (class "Default")
      (node (ref "U11") (pin "8") (pinfunction "G5_8") (pintype "input"))
    )
    (net (code "79") (name "/IN86") (class "Default")
      (node (ref "U11") (pin "9") (pinfunction "G6_9") (pintype "input"))
    )
    (net (code "80") (name "/IN87") (class "Default")
      (node (ref "U11") (pin "10") (pinfunction "G7_10") (pintype "input"))
    )
    (net (code "81") (name "/IN90") (class "Default")
      (node (ref "U11") (pin "16") (pinfunction "B0_16") (pintype "input"))
    )
    (net (code "82") (name "/IN91") (class "Default")
      (node (ref "U11") (pin "17") (pinfunction "B1_17") (pintype "input"))
    )
    (net (code "83") (name "/IN92") (class "Default")
      (node (ref "U11") (pin "18") (pinfunction "B2_18") (pintype "input"))
    )
    (net (code "84") (name "/IN93") (class "Default")
      (node (ref "U11") (pin "19") (pinfunction "B3_19") (pintype "input"))
    )
    (net (code "85") (name "/IN94") (class "Default")
      (node (ref "U11") (pin "20") (pinfunction "B4_20") (pintype "input"))
    )
    (net (code "86") (name "/IN95") (class "Default")
      (node (ref "U11") (pin "21") (pinfunction "B5_21") (pintype "input"))
    )
    (net (code "87") (name "/IN96") (class "Default")
      (node (ref "U11") (pin "22") (pinfunction "B6_22") (pintype "input"))
    )
    (net (code "88") (name "/IN97") (class "Default")
      (node (ref "U11") (pin "23") (pinfunction "B7_23") (pintype "input"))
    )
    (net (code "89") (name "/IO1") (class "Default")
      (node (ref "R10") (pin "2") (pinfunction "2_2") (pintype "passive"))
      (node (ref "R11") (pin "2") (pinfunction "2_2") (pintype "passive"))
      (node (ref "U9") (pin "33") (pinfunction "~{IOR}_33") (pintype "output"))
    )
    (net (code "90") (name "/IO1M") (class "Default")
      (node (ref "C1") (pin "1") (pinfunction "1_1") (pintype "passive"))
      (node (ref "R10") (pin "1") (pinfunction "1_1") (pintype "passive"))
      (node (ref "R41") (pin "1") (pinfunction "1_1") (pintype "passive"))
      (node (ref "R59") (pin "1") (pinfunction "1_1") (pintype "passive"))
      (node (ref "U1") (pin "2") (pinfunction "-INA_2") (pintype "passive"))
    )
    (net (code "91") (name "/IO1P") (class "Default")
      (node (ref "R1") (pin "1") (pinfunction "1_1") (pintype "passive"))
      (node (ref "R11") (pin "1") (pinfunction "1_1") (pintype "passive"))
      (node (ref "R32") (pin "1") (pinfunction "TOP_1") (pintype "passive"))
      (node (ref "U1") (pin "3") (pinfunction "+INA_3") (pintype "passive"))
    )
    (net (code "92") (name "/IO2") (class "Default")
      (node (ref "R12") (pin "2") (pinfunction "2_2") (pintype "passive"))
      (node (ref "R13") (pin "2") (pinfunction "2_2") (pintype "passive"))
      (node (ref "U9") (pin "31") (pinfunction "~{IOG}_31") (pintype "output"))
    )
    (net (code "93") (name "/IO2M") (class "Default")
      (node (ref "C2") (pin "1") (pinfunction "1_1") (pintype "passive"))
      (node (ref "R12") (pin "1") (pinfunction "1_1") (pintype "passive"))
      (node (ref "R42") (pin "1") (pinfunction "1_1") (pintype "passive"))
      (node (ref "R60") (pin "1") (pinfunction "1_1") (pintype "passive"))
      (node (ref "U1") (pin "6") (pinfunction "-INB_6") (pintype "passive"))
    )
    (net (code "94") (name "/IO2P") (class "Default")
      (node (ref "R13") (pin "1") (pinfunction "1_1") (pintype "passive"))
      (node (ref "R2") (pin "1") (pinfunction "1_1") (pintype "passive"))
      (node (ref "R33") (pin "1") (pinfunction "TOP_1") (pintype "passive"))
      (node (ref "U1") (pin "5") (pinfunction "+INB_5") (pintype "passive"))
    )
    (net (code "95") (name "/IO3") (class "Default")
      (node (ref "R14") (pin "2") (pinfunction "2_2") (pintype "passive"))
      (node (ref "R15") (pin "2") (pinfunction "2_2") (pintype "passive"))
      (node (ref "U9") (pin "27") (pinfunction "~{IOB}_27") (pintype "output"))
    )
    (net (code "96") (name "/IO3M") (class "Default")
      (node (ref "C3") (pin "1") (pinfunction "1_1") (pintype "passive"))
      (node (ref "R14") (pin "1") (pinfunction "1_1") (pintype "passive"))
      (node (ref "R43") (pin "1") (pinfunction "1_1") (pintype "passive"))
      (node (ref "R61") (pin "1") (pinfunction "1_1") (pintype "passive"))
      (node (ref "U2") (pin "2") (pinfunction "-INA_2") (pintype "passive"))
    )
    (net (code "97") (name "/IO3P") (class "Default")
      (node (ref "R15") (pin "1") (pinfunction "1_1") (pintype "passive"))
      (node (ref "R3") (pin "1") (pinfunction "1_1") (pintype "passive"))
      (node (ref "R34") (pin "1") (pinfunction "TOP_1") (pintype "passive"))
      (node (ref "U2") (pin "3") (pinfunction "+INA_3") (pintype "passive"))
    )
    (net (code "98") (name "/IO4") (class "Default")
      (node (ref "R16") (pin "2") (pinfunction "2_2") (pintype "passive"))
      (node (ref "R17") (pin "2") (pinfunction "2_2") (pintype "passive"))
      (node (ref "U10") (pin "33") (pinfunction "~{IOR}_33") (pintype "output"))
    )
    (net (code "99") (name "/IO4M") (class "Default")
      (node (ref "C4") (pin "1") (pinfunction "1_1") (pintype "passive"))
      (node (ref "R16") (pin "1") (pinfunction "1_1") (pintype "passive"))
      (node (ref "R44") (pin "1") (pinfunction "1_1") (pintype "passive"))
      (node (ref "R62") (pin "1") (pinfunction "1_1") (pintype "passive"))
      (node (ref "U2") (pin "6") (pinfunction "-INB_6") (pintype "passive"))
    )
    (net (code "100") (name "/IO4P") (class "Default")
      (node (ref "R17") (pin "1") (pinfunction "1_1") (pintype "passive"))
      (node (ref "R35") (pin "1") (pinfunction "TOP_1") (pintype "passive"))
      (node (ref "R4") (pin "1") (pinfunction "1_1") (pintype "passive"))
      (node (ref "U2") (pin "5") (pinfunction "+INB_5") (pintype "passive"))
    )
    (net (code "101") (name "/IO5") (class "Default")
      (node (ref "R18") (pin "2") (pinfunction "2_2") (pintype "passive"))
      (node (ref "R19") (pin "2") (pinfunction "2_2") (pintype "passive"))
      (node (ref "U10") (pin "31") (pinfunction "~{IOG}_31") (pintype "output"))
    )
    (net (code "102") (name "/IO5M") (class "Default")
      (node (ref "C6") (pin "1") (pinfunction "1_1") (pintype "passive"))
      (node (ref "R18") (pin "1") (pinfunction "1_1") (pintype "passive"))
      (node (ref "R63") (pin "1") (pinfunction "1_1") (pintype "passive"))
      (node (ref "R68") (pin "1") (pinfunction "1_1") (pintype "passive"))
      (node (ref "U4") (pin "2") (pinfunction "-INA_2") (pintype "passive"))
    )
    (net (code "103") (name "/IO5P") (class "Default")
      (node (ref "R19") (pin "1") (pinfunction "1_1") (pintype "passive"))
      (node (ref "R36") (pin "1") (pinfunction "TOP_1") (pintype "passive"))
      (node (ref "R5") (pin "1") (pinfunction "1_1") (pintype "passive"))
      (node (ref "U4") (pin "3") (pinfunction "+INA_3") (pintype "passive"))
    )
    (net (code "104") (name "/IO6") (class "Default")
      (node (ref "R20") (pin "2") (pinfunction "2_2") (pintype "passive"))
      (node (ref "R21") (pin "2") (pinfunction "2_2") (pintype "passive"))
      (node (ref "U10") (pin "27") (pinfunction "~{IOB}_27") (pintype "output"))
    )
    (net (code "105") (name "/IO6M") (class "Default")
      (node (ref "C7") (pin "1") (pinfunction "1_1") (pintype "passive"))
      (node (ref "R20") (pin "1") (pinfunction "1_1") (pintype "passive"))
      (node (ref "R64") (pin "1") (pinfunction "1_1") (pintype "passive"))
      (node (ref "R69") (pin "1") (pinfunction "1_1") (pintype "passive"))
      (node (ref "U4") (pin "6") (pinfunction "-INB_6") (pintype "passive"))
    )
    (net (code "106") (name "/IO6P") (class "Default")
      (node (ref "R21") (pin "1") (pinfunction "1_1") (pintype "passive"))
      (node (ref "R37") (pin "1") (pinfunction "TOP_1") (pintype "passive"))
      (node (ref "R6") (pin "1") (pinfunction "1_1") (pintype "passive"))
      (node (ref "U4") (pin "5") (pinfunction "+INB_5") (pintype "passive"))
    )
    (net (code "107") (name "/IO7") (class "Default")
      (node (ref "R22") (pin "2") (pinfunction "2_2") (pintype "passive"))
      (node (ref "R23") (pin "2") (pinfunction "2_2") (pintype "passive"))
      (node (ref "U11") (pin "33") (pinfunction "~{IOR}_33") (pintype "output"))
    )
    (net (code "108") (name "/IO7M") (class "Default")
      (node (ref "C8") (pin "1") (pinfunction "1_1") (pintype "passive"))
      (node (ref "R22") (pin "1") (pinfunction "1_1") (pintype "passive"))
      (node (ref "R65") (pin "1") (pinfunction "1_1") (pintype "passive"))
      (node (ref "R70") (pin "1") (pinfunction "1_1") (pintype "passive"))
      (node (ref "U3") (pin "2") (pinfunction "-INA_2") (pintype "passive"))
    )
    (net (code "109") (name "/IO7P") (class "Default")
      (node (ref "R23") (pin "1") (pinfunction "1_1") (pintype "passive"))
      (node (ref "R38") (pin "1") (pinfunction "TOP_1") (pintype "passive"))
      (node (ref "R7") (pin "1") (pinfunction "1_1") (pintype "passive"))
      (node (ref "U3") (pin "3") (pinfunction "+INA_3") (pintype "passive"))
    )
    (net (code "110") (name "/IO8") (class "Default")
      (node (ref "R24") (pin "2") (pinfunction "2_2") (pintype "passive"))
      (node (ref "R25") (pin "2") (pinfunction "2_2") (pintype "passive"))
      (node (ref "U11") (pin "31") (pinfunction "~{IOG}_31") (pintype "output"))
    )
    (net (code "111") (name "/IO8M") (class "Default")
      (node (ref "C9") (pin "1") (pinfunction "1_1") (pintype "passive"))
      (node (ref "R24") (pin "1") (pinfunction "1_1") (pintype "passive"))
      (node (ref "R66") (pin "1") (pinfunction "1_1") (pintype "passive"))
      (node (ref "R71") (pin "1") (pinfunction "1_1") (pintype "passive"))
      (node (ref "U3") (pin "6") (pinfunction "-INB_6") (pintype "passive"))
    )
    (net (code "112") (name "/IO8P") (class "Default")
      (node (ref "R25") (pin "1") (pinfunction "1_1") (pintype "passive"))
      (node (ref "R39") (pin "1") (pinfunction "TOP_1") (pintype "passive"))
      (node (ref "R8") (pin "1") (pinfunction "1_1") (pintype "passive"))
      (node (ref "U3") (pin "5") (pinfunction "+INB_5") (pintype "passive"))
    )
    (net (code "113") (name "/IO9") (class "Default")
      (node (ref "R26") (pin "2") (pinfunction "2_2") (pintype "passive"))
      (node (ref "R27") (pin "2") (pinfunction "2_2") (pintype "passive"))
      (node (ref "U11") (pin "27") (pinfunction "~{IOB}_27") (pintype "output"))
    )
    (net (code "114") (name "/IO9M") (class "Default")
      (node (ref "C10") (pin "1") (pinfunction "1_1") (pintype "passive"))
      (node (ref "R26") (pin "1") (pinfunction "1_1") (pintype "passive"))
      (node (ref "R67") (pin "1") (pinfunction "1_1") (pintype "passive"))
      (node (ref "R72") (pin "1") (pinfunction "1_1") (pintype "passive"))
      (node (ref "U5") (pin "4") (pinfunction "VIN-_4") (pintype "passive"))
    )
    (net (code "115") (name "/IO9P") (class "Default")
      (node (ref "R27") (pin "1") (pinfunction "1_1") (pintype "passive"))
      (node (ref "R40") (pin "1") (pinfunction "TOP_1") (pintype "passive"))
      (node (ref "R9") (pin "1") (pinfunction "1_1") (pintype "passive"))
      (node (ref "U5") (pin "3") (pinfunction "VIN+_3") (pintype "passive"))
    )
    (net (code "116") (name "/OP193") (class "Default")
      (node (ref "C21") (pin "2") (pinfunction "2_2") (pintype "passive"))
      (node (ref "R74") (pin "2") (pinfunction "2_2") (pintype "passive"))
      (node (ref "U7") (pin "3") (pinfunction "IN+_3") (pintype "passive"))
    )
    (net (code "117") (name "/OUT1") (class "Default")
      (node (ref "C1") (pin "2") (pinfunction "2_2") (pintype "passive"))
      (node (ref "R28") (pin "1") (pinfunction "TOP_1") (pintype "passive"))
      (node (ref "R59") (pin "2") (pinfunction "2_2") (pintype "passive"))
      (node (ref "U1") (pin "1") (pinfunction "OUTA_1") (pintype "passive"))
    )
    (net (code "118") (name "/OUT2") (class "Default")
      (node (ref "C2") (pin "2") (pinfunction "2_2") (pintype "passive"))
      (node (ref "R29") (pin "1") (pinfunction "TOP_1") (pintype "passive"))
      (node (ref "R60") (pin "2") (pinfunction "2_2") (pintype "passive"))
      (node (ref "U1") (pin "7") (pinfunction "OUTB_7") (pintype "passive"))
    )
    (net (code "119") (name "/OUT3") (class "Default")
      (node (ref "C3") (pin "2") (pinfunction "2_2") (pintype "passive"))
      (node (ref "R30") (pin "1") (pinfunction "TOP_1") (pintype "passive"))
      (node (ref "R61") (pin "2") (pinfunction "2_2") (pintype "passive"))
      (node (ref "U2") (pin "1") (pinfunction "OUTA_1") (pintype "passive"))
    )
    (net (code "120") (name "/OUT4") (class "Default")
      (node (ref "C4") (pin "2") (pinfunction "2_2") (pintype "passive"))
      (node (ref "R31") (pin "1") (pinfunction "TOP_1") (pintype "passive"))
      (node (ref "R62") (pin "2") (pinfunction "2_2") (pintype "passive"))
      (node (ref "U2") (pin "7") (pinfunction "OUTB_7") (pintype "passive"))
    )
    (net (code "121") (name "/OUT5") (class "Default")
      (node (ref "C6") (pin "2") (pinfunction "2_2") (pintype "passive"))
      (node (ref "R54") (pin "1") (pinfunction "TOP_1") (pintype "passive"))
      (node (ref "R63") (pin "2") (pinfunction "2_2") (pintype "passive"))
      (node (ref "U4") (pin "1") (pinfunction "OUTA_1") (pintype "passive"))
    )
    (net (code "122") (name "/OUT6") (class "Default")
      (node (ref "C7") (pin "2") (pinfunction "2_2") (pintype "passive"))
      (node (ref "R55") (pin "1") (pinfunction "TOP_1") (pintype "passive"))
      (node (ref "R64") (pin "2") (pinfunction "2_2") (pintype "passive"))
      (node (ref "U4") (pin "7") (pinfunction "OUTB_7") (pintype "passive"))
    )
    (net (code "123") (name "/OUT7") (class "Default")
      (node (ref "C8") (pin "2") (pinfunction "2_2") (pintype "passive"))
      (node (ref "R56") (pin "1") (pinfunction "TOP_1") (pintype "passive"))
      (node (ref "R65") (pin "2") (pinfunction "2_2") (pintype "passive"))
      (node (ref "U3") (pin "1") (pinfunction "OUTA_1") (pintype "passive"))
    )
    (net (code "124") (name "/OUT8") (class "Default")
      (node (ref "C9") (pin "2") (pinfunction "2_2") (pintype "passive"))
      (node (ref "R57") (pin "1") (pinfunction "TOP_1") (pintype "passive"))
      (node (ref "R66") (pin "2") (pinfunction "2_2") (pintype "passive"))
      (node (ref "U3") (pin "7") (pinfunction "OUTB_7") (pintype "passive"))
    )
    (net (code "125") (name "/OUT9") (class "Default")
      (node (ref "C10") (pin "2") (pinfunction "2_2") (pintype "passive"))
      (node (ref "R58") (pin "1") (pinfunction "TOP_1") (pintype "passive"))
      (node (ref "R67") (pin "2") (pinfunction "2_2") (pintype "passive"))
      (node (ref "U5") (pin "1") (pinfunction "VOUT_1") (pintype "passive"))
    )
    (net (code "126") (name "/PSAVE1") (class "Default")
      (node (ref "U9") (pin "38") (pinfunction "~{PSAVE}_38") (pintype "input"))
    )
    (net (code "127") (name "/PSAVE2") (class "Default")
      (node (ref "U10") (pin "38") (pinfunction "~{PSAVE}_38") (pintype "input"))
    )
    (net (code "128") (name "/PSAVE3") (class "Default")
      (node (ref "U11") (pin "38") (pinfunction "~{PSAVE}_38") (pintype "input"))
    )
    (net (code "129") (name "/RSET1") (class "Default")
      (node (ref "R75") (pin "2") (pinfunction "2_2") (pintype "passive"))
      (node (ref "U9") (pin "37") (pinfunction "RSET_37") (pintype "input"))
    )
    (net (code "130") (name "/RSET2") (class "Default")
      (node (ref "R76") (pin "2") (pinfunction "2_2") (pintype "passive"))
      (node (ref "U10") (pin "37") (pinfunction "RSET_37") (pintype "input"))
    )
    (net (code "131") (name "/RSET3") (class "Default")
      (node (ref "R77") (pin "2") (pinfunction "2_2") (pintype "passive"))
      (node (ref "U11") (pin "37") (pinfunction "RSET_37") (pintype "input"))
    )
    (net (code "132") (name "/VREF") (class "Default")
      (node (ref "U10") (pin "36") (pinfunction "VREF_36") (pintype "input"))
      (node (ref "U11") (pin "36") (pinfunction "VREF_36") (pintype "input"))
      (node (ref "U7") (pin "2") (pinfunction "IN-_2") (pintype "passive"))
      (node (ref "U7") (pin "6") (pinfunction "OUT_6") (pintype "passive"))
      (node (ref "U9") (pin "36") (pinfunction "VREF_36") (pintype "input"))
    )
    (net (code "133") (name "/VUP") (class "Default")
      (node (ref "C11") (pin "2") (pinfunction "2_2") (pintype "passive"))
      (node (ref "R1") (pin "2") (pinfunction "2_2") (pintype "passive"))
      (node (ref "R2") (pin "2") (pinfunction "2_2") (pintype "passive"))
      (node (ref "R3") (pin "2") (pinfunction "2_2") (pintype "passive"))
      (node (ref "R4") (pin "2") (pinfunction "2_2") (pintype "passive"))
      (node (ref "R5") (pin "2") (pinfunction "2_2") (pintype "passive"))
      (node (ref "R6") (pin "2") (pinfunction "2_2") (pintype "passive"))
      (node (ref "R7") (pin "2") (pinfunction "2_2") (pintype "passive"))
      (node (ref "R8") (pin "2") (pinfunction "2_2") (pintype "passive"))
      (node (ref "R9") (pin "2") (pinfunction "2_2") (pintype "passive"))
      (node (ref "U6") (pin "2") (pinfunction "OUT_2") (pintype "passive"))
    )
    (net (code "134") (name "Net-(R28-TAP)") (class "Default")
      (node (ref "R28") (pin "3") (pinfunction "TAP_3") (pintype "passive"))
      (node (ref "R41") (pin "2") (pinfunction "2_2") (pintype "passive"))
    )
    (net (code "135") (name "Net-(R29-TAP)") (class "Default")
      (node (ref "R29") (pin "3") (pinfunction "TAP_3") (pintype "passive"))
      (node (ref "R42") (pin "2") (pinfunction "2_2") (pintype "passive"))
    )
    (net (code "136") (name "Net-(R30-TAP)") (class "Default")
      (node (ref "R30") (pin "3") (pinfunction "TAP_3") (pintype "passive"))
      (node (ref "R43") (pin "2") (pinfunction "2_2") (pintype "passive"))
    )
    (net (code "137") (name "Net-(R31-TAP)") (class "Default")
      (node (ref "R31") (pin "3") (pinfunction "TAP_3") (pintype "passive"))
      (node (ref "R44") (pin "2") (pinfunction "2_2") (pintype "passive"))
    )
    (net (code "138") (name "Net-(R32-TAP)") (class "Default")
      (node (ref "R32") (pin "3") (pinfunction "TAP_3") (pintype "passive"))
      (node (ref "R45") (pin "2") (pinfunction "2_2") (pintype "passive"))
    )
    (net (code "139") (name "Net-(R33-TAP)") (class "Default")
      (node (ref "R33") (pin "3") (pinfunction "TAP_3") (pintype "passive"))
      (node (ref "R46") (pin "2") (pinfunction "2_2") (pintype "passive"))
    )
    (net (code "140") (name "Net-(R34-TAP)") (class "Default")
      (node (ref "R34") (pin "3") (pinfunction "TAP_3") (pintype "passive"))
      (node (ref "R47") (pin "2") (pinfunction "2_2") (pintype "passive"))
    )
    (net (code "141") (name "Net-(R35-TAP)") (class "Default")
      (node (ref "R35") (pin "3") (pinfunction "TAP_3") (pintype "passive"))
      (node (ref "R48") (pin "2") (pinfunction "2_2") (pintype "passive"))
    )
    (net (code "142") (name "Net-(R36-TAP)") (class "Default")
      (node (ref "R36") (pin "3") (pinfunction "TAP_3") (pintype "passive"))
      (node (ref "R49") (pin "2") (pinfunction "2_2") (pintype "passive"))
    )
    (net (code "143") (name "Net-(R37-TAP)") (class "Default")
      (node (ref "R37") (pin "3") (pinfunction "TAP_3") (pintype "passive"))
      (node (ref "R50") (pin "2") (pinfunction "2_2") (pintype "passive"))
    )
    (net (code "144") (name "Net-(R38-TAP)") (class "Default")
      (node (ref "R38") (pin "3") (pinfunction "TAP_3") (pintype "passive"))
      (node (ref "R51") (pin "2") (pinfunction "2_2") (pintype "passive"))
    )
    (net (code "145") (name "Net-(R39-TAP)") (class "Default")
      (node (ref "R39") (pin "3") (pinfunction "TAP_3") (pintype "passive"))
      (node (ref "R52") (pin "2") (pinfunction "2_2") (pintype "passive"))
    )
    (net (code "146") (name "Net-(R40-TAP)") (class "Default")
      (node (ref "R40") (pin "3") (pinfunction "TAP_3") (pintype "passive"))
      (node (ref "R53") (pin "2") (pinfunction "2_2") (pintype "passive"))
    )
    (net (code "147") (name "Net-(R54-TAP)") (class "Default")
      (node (ref "R54") (pin "3") (pinfunction "TAP_3") (pintype "passive"))
      (node (ref "R68") (pin "2") (pinfunction "2_2") (pintype "passive"))
    )
    (net (code "148") (name "Net-(R55-TAP)") (class "Default")
      (node (ref "R55") (pin "3") (pinfunction "TAP_3") (pintype "passive"))
      (node (ref "R69") (pin "2") (pinfunction "2_2") (pintype "passive"))
    )
    (net (code "149") (name "Net-(R56-TAP)") (class "Default")
      (node (ref "R56") (pin "3") (pinfunction "TAP_3") (pintype "passive"))
      (node (ref "R70") (pin "2") (pinfunction "2_2") (pintype "passive"))
    )
    (net (code "150") (name "Net-(R57-TAP)") (class "Default")
      (node (ref "R57") (pin "3") (pinfunction "TAP_3") (pintype "passive"))
      (node (ref "R71") (pin "2") (pinfunction "2_2") (pintype "passive"))
    )
    (net (code "151") (name "Net-(R58-TAP)") (class "Default")
      (node (ref "R58") (pin "3") (pinfunction "TAP_3") (pintype "passive"))
      (node (ref "R72") (pin "2") (pinfunction "2_2") (pintype "passive"))
    )
    (net (code "152") (name "Net-(U8-V+)") (class "Default")
      (node (ref "R73") (pin "1") (pinfunction "1_1") (pintype "passive"))
      (node (ref "R74") (pin "1") (pinfunction "1_1") (pintype "passive"))
      (node (ref "U8") (pin "1") (pinfunction "V+_1") (pintype "passive"))
    )
    (net (code "153") (name "unconnected-(R28-BOT-Pad2)") (class "Default")
      (node (ref "R28") (pin "2") (pinfunction "BOT_2") (pintype "passive+no_connect"))
    )
    (net (code "154") (name "unconnected-(R29-BOT-Pad2)") (class "Default")
      (node (ref "R29") (pin "2") (pinfunction "BOT_2") (pintype "passive+no_connect"))
    )
    (net (code "155") (name "unconnected-(R30-BOT-Pad2)") (class "Default")
      (node (ref "R30") (pin "2") (pinfunction "BOT_2") (pintype "passive+no_connect"))
    )
    (net (code "156") (name "unconnected-(R31-BOT-Pad2)") (class "Default")
      (node (ref "R31") (pin "2") (pinfunction "BOT_2") (pintype "passive+no_connect"))
    )
    (net (code "157") (name "unconnected-(R32-BOT-Pad2)") (class "Default")
      (node (ref "R32") (pin "2") (pinfunction "BOT_2") (pintype "passive+no_connect"))
    )
    (net (code "158") (name "unconnected-(R33-BOT-Pad2)") (class "Default")
      (node (ref "R33") (pin "2") (pinfunction "BOT_2") (pintype "passive+no_connect"))
    )
    (net (code "159") (name "unconnected-(R34-BOT-Pad2)") (class "Default")
      (node (ref "R34") (pin "2") (pinfunction "BOT_2") (pintype "passive+no_connect"))
    )
    (net (code "160") (name "unconnected-(R35-BOT-Pad2)") (class "Default")
      (node (ref "R35") (pin "2") (pinfunction "BOT_2") (pintype "passive+no_connect"))
    )
    (net (code "161") (name "unconnected-(R36-BOT-Pad2)") (class "Default")
      (node (ref "R36") (pin "2") (pinfunction "BOT_2") (pintype "passive+no_connect"))
    )
    (net (code "162") (name "unconnected-(R37-BOT-Pad2)") (class "Default")
      (node (ref "R37") (pin "2") (pinfunction "BOT_2") (pintype "passive+no_connect"))
    )
    (net (code "163") (name "unconnected-(R38-BOT-Pad2)") (class "Default")
      (node (ref "R38") (pin "2") (pinfunction "BOT_2") (pintype "passive+no_connect"))
    )
    (net (code "164") (name "unconnected-(R39-BOT-Pad2)") (class "Default")
      (node (ref "R39") (pin "2") (pinfunction "BOT_2") (pintype "passive+no_connect"))
    )
    (net (code "165") (name "unconnected-(R40-BOT-Pad2)") (class "Default")
      (node (ref "R40") (pin "2") (pinfunction "BOT_2") (pintype "passive+no_connect"))
    )
    (net (code "166") (name "unconnected-(R54-BOT-Pad2)") (class "Default")
      (node (ref "R54") (pin "2") (pinfunction "BOT_2") (pintype "passive+no_connect"))
    )
    (net (code "167") (name "unconnected-(R55-BOT-Pad2)") (class "Default")
      (node (ref "R55") (pin "2") (pinfunction "BOT_2") (pintype "passive+no_connect"))
    )
    (net (code "168") (name "unconnected-(R56-BOT-Pad2)") (class "Default")
      (node (ref "R56") (pin "2") (pinfunction "BOT_2") (pintype "passive+no_connect"))
    )
    (net (code "169") (name "unconnected-(R57-BOT-Pad2)") (class "Default")
      (node (ref "R57") (pin "2") (pinfunction "BOT_2") (pintype "passive+no_connect"))
    )
    (net (code "170") (name "unconnected-(R58-BOT-Pad2)") (class "Default")
      (node (ref "R58") (pin "2") (pinfunction "BOT_2") (pintype "passive+no_connect"))
    )
    (net (code "171") (name "unconnected-(U7-N.C-Pad8)") (class "Default")
      (node (ref "U7") (pin "8") (pinfunction "N.C_8") (pintype "passive"))
    )
    (net (code "172") (name "unconnected-(U7-NULL-Pad1)") (class "Default")
      (node (ref "U7") (pin "1") (pinfunction "NULL_1") (pintype "passive"))
    )
    (net (code "173") (name "unconnected-(U7-NULL-Pad5)") (class "Default")
      (node (ref "U7") (pin "5") (pinfunction "NULL_5") (pintype "passive"))
    )
    (net (code "174") (name "unconnected-(U8-N.C-Pad3)") (class "Default")
      (node (ref "U8") (pin "3") (pinfunction "N.C_3") (pintype "passive+no_connect"))
    )
  )
)
